# Pcon.net
KiCad netlist of a schematic drawn in EAGLE
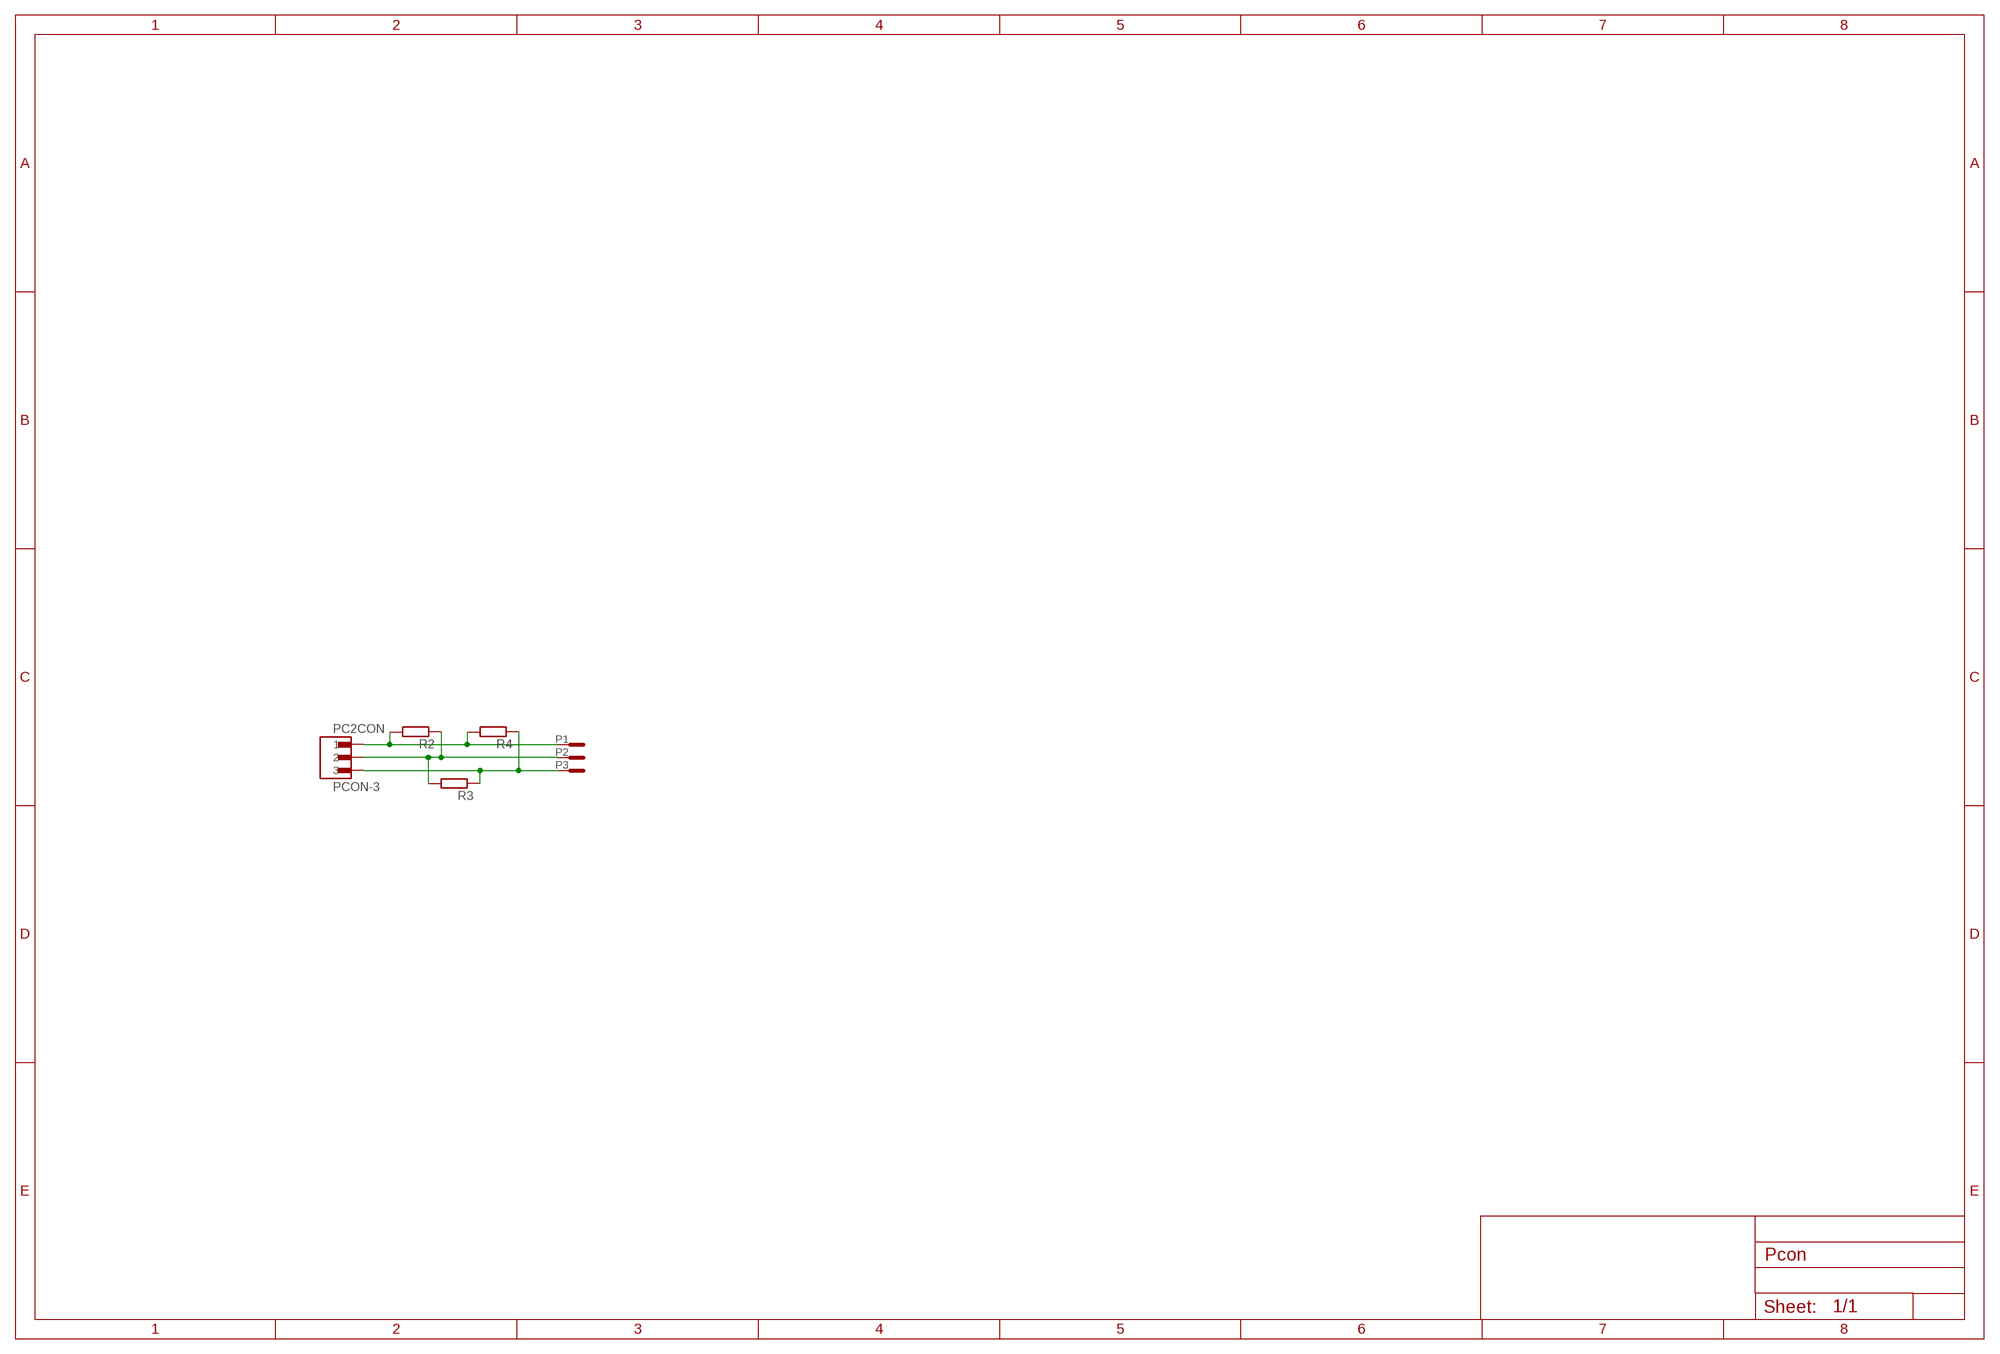
[diagram p0: schematic, sheet 1]

(export (version "E")
  (design (tool "Eeschema 10.0.6"))
  (components
    (comp (ref "PC2")
      (value "PCON-3")
      (footprint "eagle-import:PCON-3")
      (libsource (lib "eagle-import") (part "PCON-3?"))
    )
    (comp (ref "R2")
      (value "R-EU_R0603")
      (footprint "eagle-import:R0603")
      (libsource (lib "eagle-import") (part "R-EU_R0603"))
    )
    (comp (ref "R3")
      (value "R-EU_R0603")
      (footprint "eagle-import:R0603")
      (libsource (lib "eagle-import") (part "R-EU_R0603"))
    )
    (comp (ref "R4")
      (value "R-EU_R0603")
      (footprint "eagle-import:R0603")
      (libsource (lib "eagle-import") (part "R-EU_R0603"))
    )
  )
  (nets
    (net (code "1") (name "Net-(PC2B-P)") (class "Default")
      (node (ref "PC2") (pin "1") (pinfunction "1_1") (pintype "bidirectional"))
      (node (ref "PC2") (pin "P1") (pinfunction "P_P1") (pintype "bidirectional"))
      (node (ref "R2") (pin "2") (pinfunction "2_2") (pintype "passive"))
      (node (ref "R4") (pin "2") (pinfunction "2_2") (pintype "passive"))
    )
    (net (code "2") (name "Net-(PC2C-P)") (class "Default")
      (node (ref "PC2") (pin "2") (pinfunction "2_2") (pintype "bidirectional"))
      (node (ref "PC2") (pin "P2") (pinfunction "P_P2") (pintype "bidirectional"))
      (node (ref "R2") (pin "1") (pinfunction "1_1") (pintype "passive"))
      (node (ref "R3") (pin "2") (pinfunction "2_2") (pintype "passive"))
    )
    (net (code "3") (name "Net-(PC2D-P)") (class "Default")
      (node (ref "PC2") (pin "3") (pinfunction "3_3") (pintype "bidirectional"))
      (node (ref "PC2") (pin "P3") (pinfunction "P_P3") (pintype "bidirectional"))
      (node (ref "R3") (pin "1") (pinfunction "1_1") (pintype "passive"))
      (node (ref "R4") (pin "1") (pinfunction "1_1") (pintype "passive"))
    )
  )
)
